# d_00_e_04.net
KiCad netlist of a schematic drawn in EasyEDA
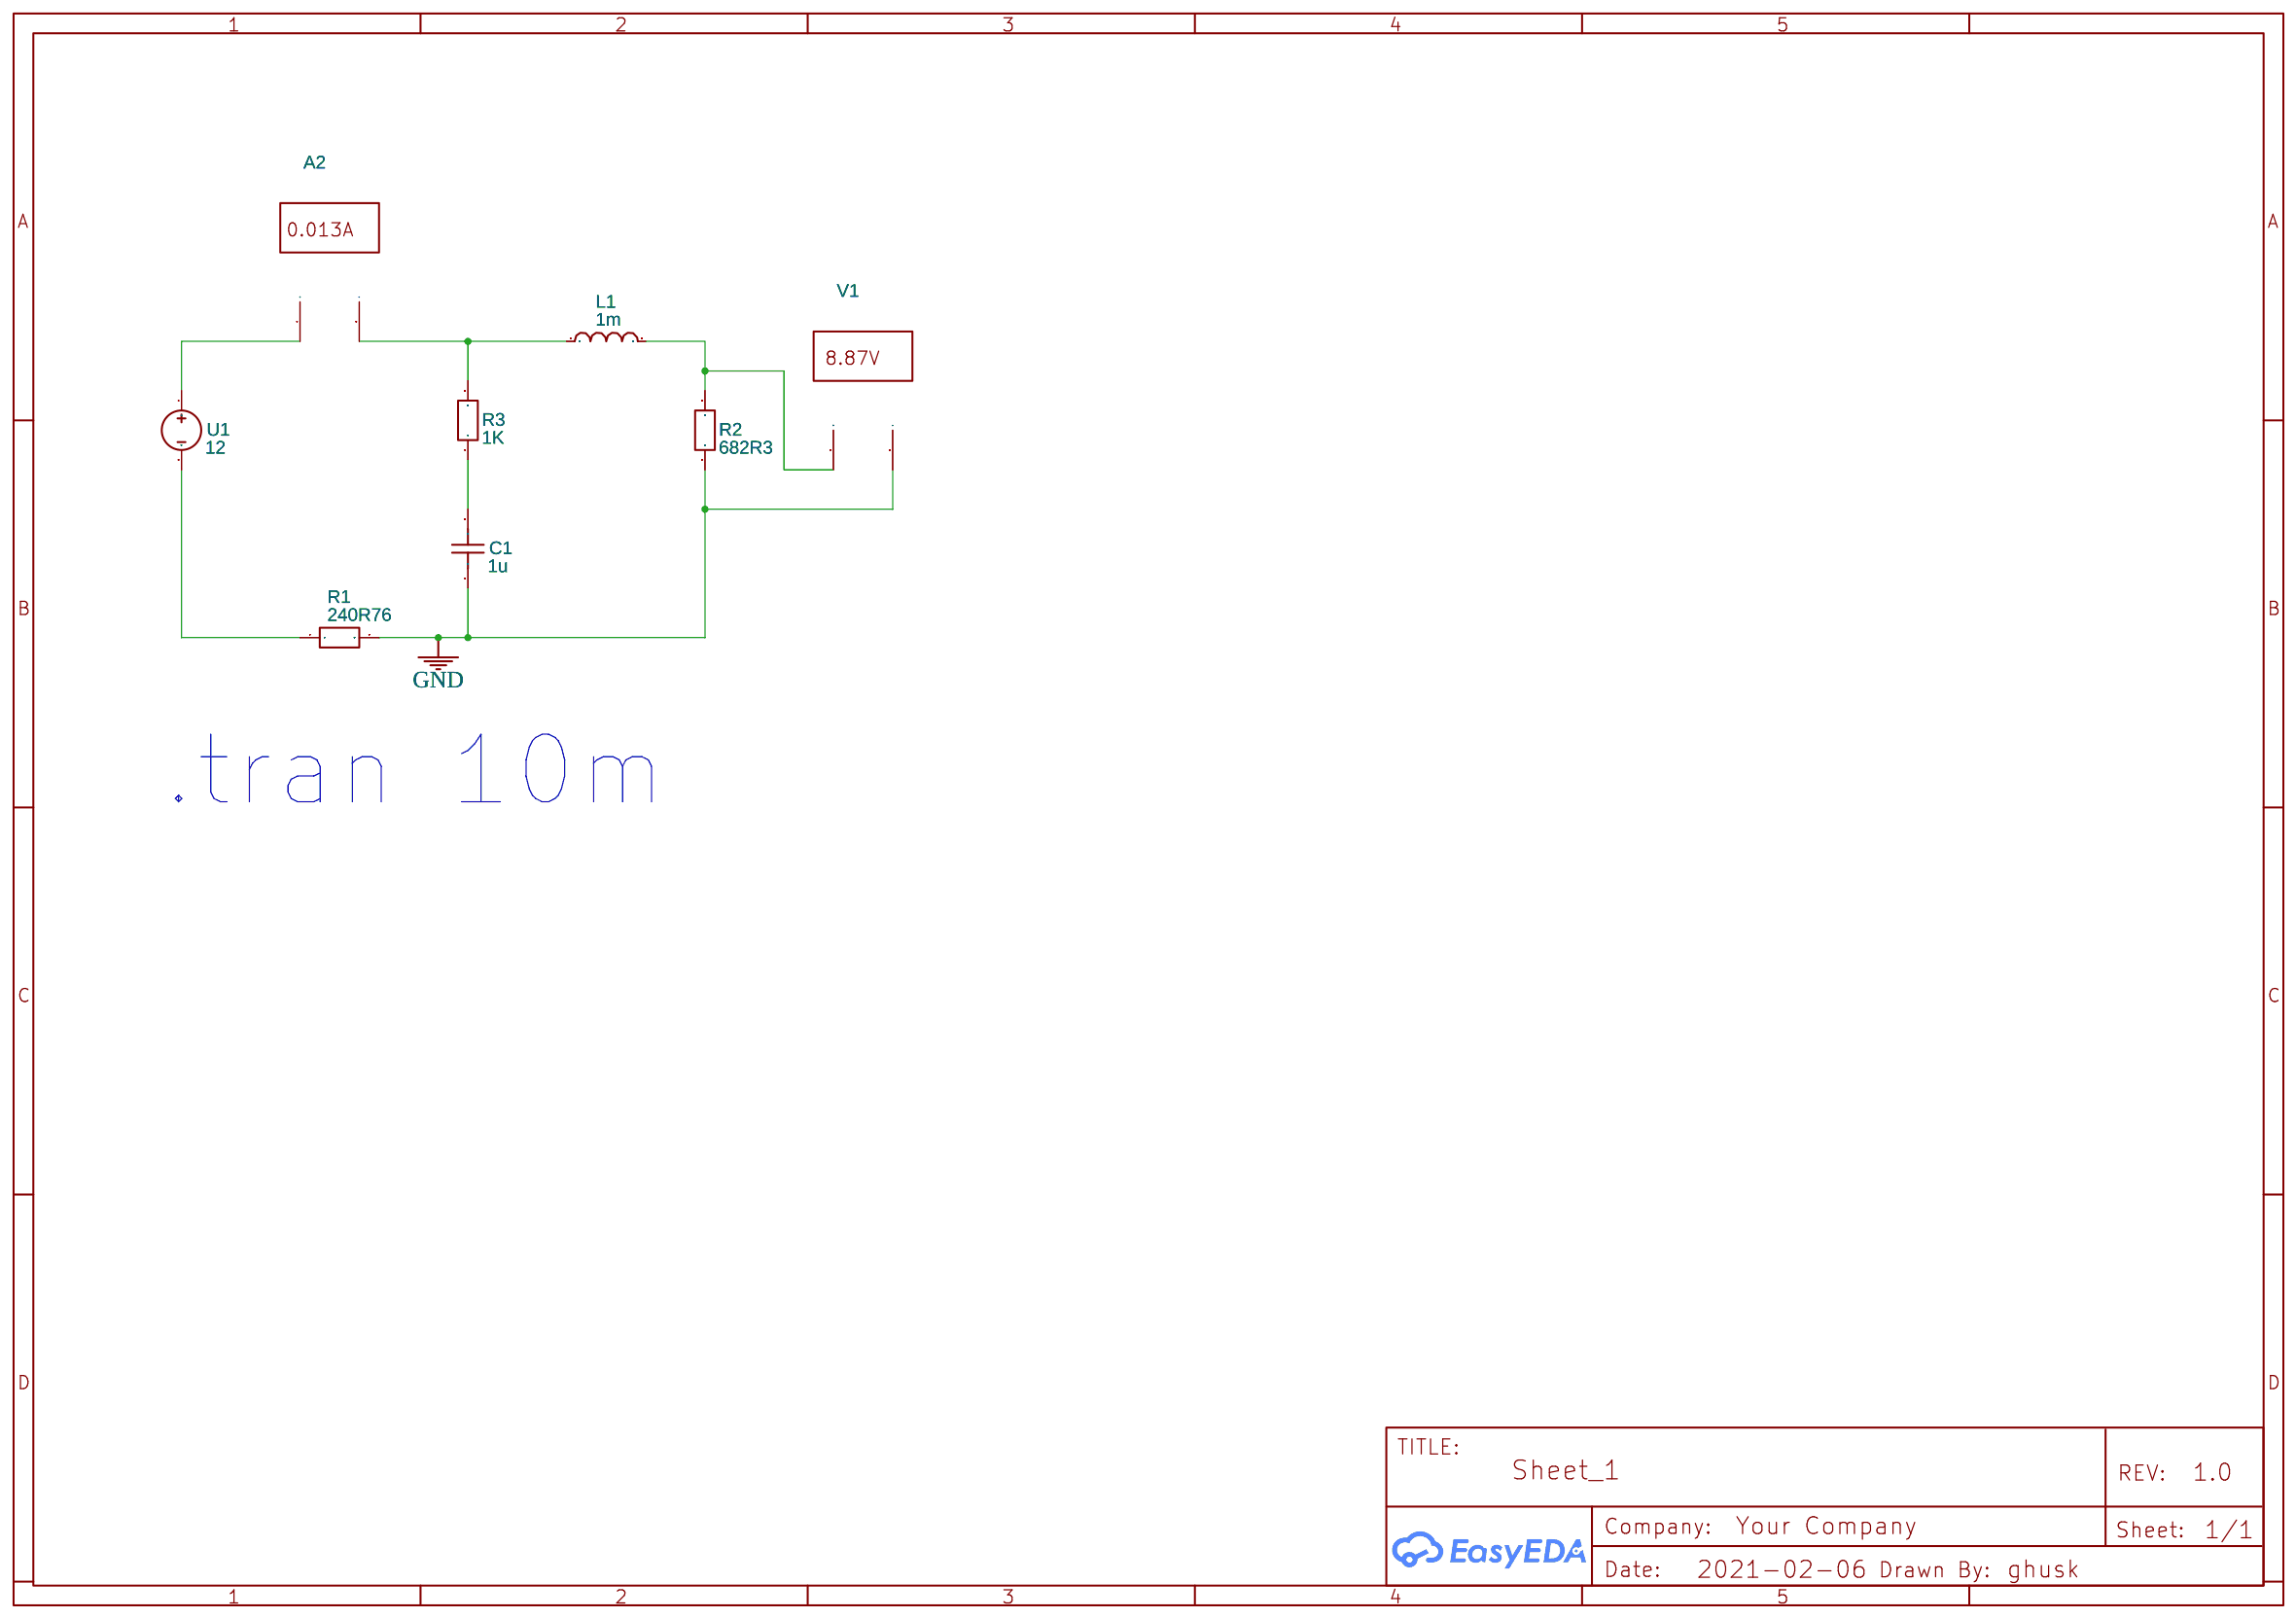
[diagram p0: schematic sheet]

(export (version "E")
  (design (tool "Eeschema 10.0.6"))
  (components
    (comp (ref "A2") (value "Multimeter") (libsource (lib "") (part "MULTIMETER")))
    (comp (ref "C1") (value "1u") (libsource (lib "") (part "Capacitor_US")))
    (comp (ref "L1") (value "1m") (libsource (lib "") (part "Inductor")))
    (comp (ref "R1") (value "240R76") (libsource (lib "") (part "Resistor_EU_1")))
    (comp (ref "R2") (value "682R3") (libsource (lib "") (part "Resistor_EU")))
    (comp (ref "R3") (value "1K") (libsource (lib "") (part "Resistor_EU")))
    (comp (ref "U1") (value "12") (libsource (lib "") (part "VDC")))
    (comp (ref "V1") (value "Multimeter") (libsource (lib "") (part "MULTIMETER_1")))
  )
  (nets
    (net (code "1") (name "GND") (class "Default")
      (node (ref "C1") (pin "1") (pinfunction "1_1") (pintype "unspecified"))
      (node (ref "R1") (pin "2") (pinfunction "2_2") (pintype "unspecified"))
      (node (ref "R2") (pin "1") (pinfunction "1_1") (pintype "unspecified"))
      (node (ref "V1") (pin "2") (pinfunction "I_2") (pintype "unspecified"))
    )
    (net (code "2") (name "Net-(A2-+)") (class "Default")
      (node (ref "A2") (pin "1") (pinfunction "+_1") (pintype "unspecified"))
      (node (ref "U1") (pin "1") (pinfunction "1_1") (pintype "unspecified"))
    )
    (net (code "3") (name "Net-(A2-I)") (class "Default")
      (node (ref "A2") (pin "2") (pinfunction "I_2") (pintype "unspecified"))
      (node (ref "L1") (pin "1") (pinfunction "1_1") (pintype "unspecified"))
      (node (ref "R3") (pin "2") (pinfunction "2_2") (pintype "unspecified"))
    )
    (net (code "4") (name "Net-(C1-Pad2)") (class "Default")
      (node (ref "C1") (pin "2") (pinfunction "2_2") (pintype "unspecified"))
      (node (ref "R3") (pin "1") (pinfunction "1_1") (pintype "unspecified"))
    )
    (net (code "5") (name "Net-(R1-Pad1)") (class "Default")
      (node (ref "R1") (pin "1") (pinfunction "1_1") (pintype "unspecified"))
      (node (ref "U1") (pin "2") (pinfunction "2_2") (pintype "unspecified"))
    )
    (net (code "6") (name "Net-(V1-+)") (class "Default")
      (node (ref "L1") (pin "2") (pinfunction "2_2") (pintype "unspecified"))
      (node (ref "R2") (pin "2") (pinfunction "2_2") (pintype "unspecified"))
      (node (ref "V1") (pin "1") (pinfunction "+_1") (pintype "unspecified"))
    )
  )
)
